# touch.net
KiCad netlist of a schematic drawn in Altium Designer
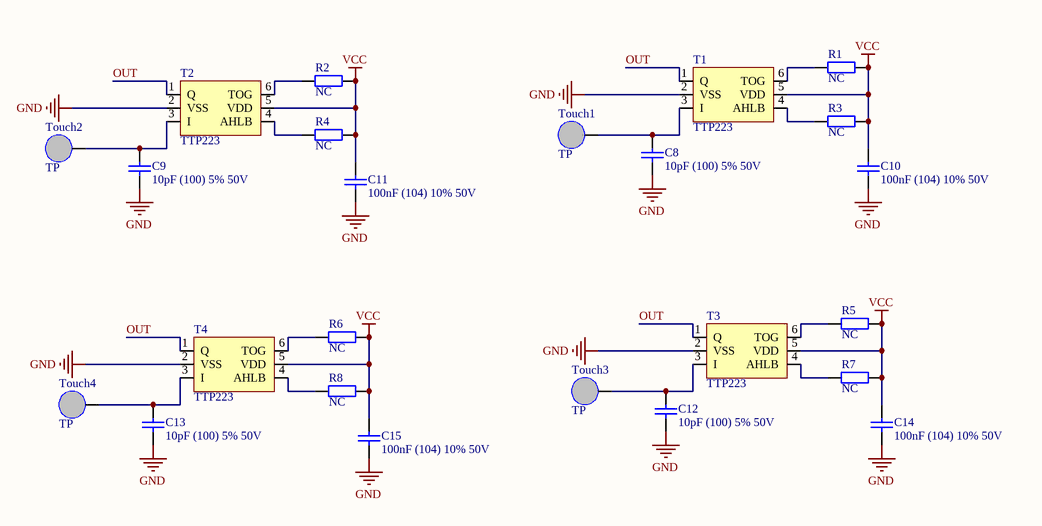
[diagram p0: touch.SchDoc]

(export (version "E")
  (design (tool "Eeschema 10.0.6"))
  (components
    (comp (ref "C8")
      (value "10pF (100) 5% 50V")
      (footprint "0603_C")
      (description "贴片电容")
      (libsource (lib "Miscellaneous Devices LC") (part "0603 10pF (100) 5% 50V"))
    )
    (comp (ref "C9")
      (value "10pF (100) 5% 50V")
      (footprint "0603_C")
      (description "贴片电容")
      (libsource (lib "Miscellaneous Devices LC") (part "0603 10pF (100) 5% 50V"))
    )
    (comp (ref "C10")
      (value "100nF (104) 10% 50V")
      (footprint "0603_C")
      (description "贴片电容")
      (libsource (lib "Miscellaneous Devices LC") (part "0603 100nF (104) 10% 50V"))
    )
    (comp (ref "C11")
      (value "100nF (104) 10% 50V")
      (footprint "0603_C")
      (description "贴片电容")
      (libsource (lib "Miscellaneous Devices LC") (part "0603 100nF (104) 10% 50V"))
    )
    (comp (ref "C12")
      (value "10pF (100) 5% 50V")
      (footprint "0603_C")
      (description "贴片电容")
      (libsource (lib "Miscellaneous Devices LC") (part "0603 10pF (100) 5% 50V"))
    )
    (comp (ref "C13")
      (value "10pF (100) 5% 50V")
      (footprint "0603_C")
      (description "贴片电容")
      (libsource (lib "Miscellaneous Devices LC") (part "0603 10pF (100) 5% 50V"))
    )
    (comp (ref "C14")
      (value "100nF (104) 10% 50V")
      (footprint "0603_C")
      (description "贴片电容")
      (libsource (lib "Miscellaneous Devices LC") (part "0603 100nF (104) 10% 50V"))
    )
    (comp (ref "C15")
      (value "100nF (104) 10% 50V")
      (footprint "0603_C")
      (description "贴片电容")
      (libsource (lib "Miscellaneous Devices LC") (part "0603 100nF (104) 10% 50V"))
    )
    (comp (ref "R1")
      (value "NC")
      (footprint "0603_R")
      (description "贴片电阻")
      (libsource (lib "Miscellaneous Devices LC") (part "0603 10KΩ (1002) 1%"))
    )
    (comp (ref "R2")
      (value "NC")
      (footprint "0603_R")
      (description "贴片电阻")
      (libsource (lib "Miscellaneous Devices LC") (part "0603 10KΩ (1002) 1%"))
    )
    (comp (ref "R3")
      (value "NC")
      (footprint "0603_R")
      (description "贴片电阻")
      (libsource (lib "Miscellaneous Devices LC") (part "0603 10KΩ (1002) 1%"))
    )
    (comp (ref "R4")
      (value "NC")
      (footprint "0603_R")
      (description "贴片电阻")
      (libsource (lib "Miscellaneous Devices LC") (part "0603 10KΩ (1002) 1%"))
    )
    (comp (ref "R5")
      (value "NC")
      (footprint "0603_R")
      (description "贴片电阻")
      (libsource (lib "Miscellaneous Devices LC") (part "0603 10KΩ (1002) 1%"))
    )
    (comp (ref "R6")
      (value "NC")
      (footprint "0603_R")
      (description "贴片电阻")
      (libsource (lib "Miscellaneous Devices LC") (part "0603 10KΩ (1002) 1%"))
    )
    (comp (ref "R7")
      (value "NC")
      (footprint "0603_R")
      (description "贴片电阻")
      (libsource (lib "Miscellaneous Devices LC") (part "0603 10KΩ (1002) 1%"))
    )
    (comp (ref "R8")
      (value "NC")
      (footprint "0603_R")
      (description "贴片电阻")
      (libsource (lib "Miscellaneous Devices LC") (part "0603 10KΩ (1002) 1%"))
    )
    (comp (ref "T1") (value "TTP223") (footprint "SOT-23-6") (libsource (lib "mylib") (part "TTP223")))
    (comp (ref "T2") (value "TTP223") (footprint "SOT-23-6") (libsource (lib "mylib") (part "TTP223")))
    (comp (ref "T3") (value "TTP223") (footprint "SOT-23-6") (libsource (lib "mylib") (part "TTP223")))
    (comp (ref "T4") (value "TTP223") (footprint "SOT-23-6") (libsource (lib "mylib") (part "TTP223")))
    (comp (ref "Touch1") (value "TP") (footprint "TP") (libsource (lib "mylib") (part "TP")))
    (comp (ref "Touch2") (value "TP") (footprint "TP") (libsource (lib "mylib") (part "TP")))
    (comp (ref "Touch3") (value "TP") (footprint "TP") (libsource (lib "mylib") (part "TP")))
    (comp (ref "Touch4") (value "TP") (footprint "TP") (libsource (lib "mylib") (part "TP")))
  )
  (nets
    (net (code "1") (name "/OUT") (class "Default")
      (node (ref "T1") (pin "1") (pinfunction "Q_1") (pintype "passive"))
      (node (ref "T2") (pin "1") (pinfunction "Q_1") (pintype "passive"))
      (node (ref "T3") (pin "1") (pinfunction "Q_1") (pintype "passive"))
      (node (ref "T4") (pin "1") (pinfunction "Q_1") (pintype "passive"))
    )
    (net (code "2") (name "GND") (class "Default")
      (node (ref "C10") (pin "1") (pinfunction "1_1") (pintype "passive"))
      (node (ref "C11") (pin "1") (pinfunction "1_1") (pintype "passive"))
      (node (ref "C12") (pin "1") (pinfunction "1_1") (pintype "passive"))
      (node (ref "C13") (pin "1") (pinfunction "1_1") (pintype "passive"))
      (node (ref "C14") (pin "1") (pinfunction "1_1") (pintype "passive"))
      (node (ref "C15") (pin "1") (pinfunction "1_1") (pintype "passive"))
      (node (ref "C8") (pin "1") (pinfunction "1_1") (pintype "passive"))
      (node (ref "C9") (pin "1") (pinfunction "1_1") (pintype "passive"))
      (node (ref "T1") (pin "2") (pinfunction "VSS_2") (pintype "passive"))
      (node (ref "T2") (pin "2") (pinfunction "VSS_2") (pintype "passive"))
      (node (ref "T3") (pin "2") (pinfunction "VSS_2") (pintype "passive"))
      (node (ref "T4") (pin "2") (pinfunction "VSS_2") (pintype "passive"))
    )
    (net (code "3") (name "Net-(T1-AHLB)") (class "Default")
      (node (ref "R3") (pin "1") (pinfunction "1_1") (pintype "passive"))
      (node (ref "T1") (pin "4") (pinfunction "AHLB_4") (pintype "passive"))
    )
    (net (code "4") (name "Net-(T1-I)") (class "Default")
      (node (ref "C8") (pin "2") (pinfunction "2_2") (pintype "passive"))
      (node (ref "T1") (pin "3") (pinfunction "I_3") (pintype "passive"))
      (node (ref "Touch1") (pin "1") (pinfunction "1_1") (pintype "passive"))
    )
    (net (code "5") (name "Net-(T1-TOG)") (class "Default")
      (node (ref "R1") (pin "1") (pinfunction "1_1") (pintype "passive"))
      (node (ref "T1") (pin "6") (pinfunction "TOG_6") (pintype "passive"))
    )
    (net (code "6") (name "Net-(T2-AHLB)") (class "Default")
      (node (ref "R4") (pin "1") (pinfunction "1_1") (pintype "passive"))
      (node (ref "T2") (pin "4") (pinfunction "AHLB_4") (pintype "passive"))
    )
    (net (code "7") (name "Net-(T2-I)") (class "Default")
      (node (ref "C9") (pin "2") (pinfunction "2_2") (pintype "passive"))
      (node (ref "T2") (pin "3") (pinfunction "I_3") (pintype "passive"))
      (node (ref "Touch2") (pin "1") (pinfunction "1_1") (pintype "passive"))
    )
    (net (code "8") (name "Net-(T2-TOG)") (class "Default")
      (node (ref "R2") (pin "1") (pinfunction "1_1") (pintype "passive"))
      (node (ref "T2") (pin "6") (pinfunction "TOG_6") (pintype "passive"))
    )
    (net (code "9") (name "Net-(T3-AHLB)") (class "Default")
      (node (ref "R7") (pin "1") (pinfunction "1_1") (pintype "passive"))
      (node (ref "T3") (pin "4") (pinfunction "AHLB_4") (pintype "passive"))
    )
    (net (code "10") (name "Net-(T3-I)") (class "Default")
      (node (ref "C12") (pin "2") (pinfunction "2_2") (pintype "passive"))
      (node (ref "T3") (pin "3") (pinfunction "I_3") (pintype "passive"))
      (node (ref "Touch3") (pin "1") (pinfunction "1_1") (pintype "passive"))
    )
    (net (code "11") (name "Net-(T3-TOG)") (class "Default")
      (node (ref "R5") (pin "1") (pinfunction "1_1") (pintype "passive"))
      (node (ref "T3") (pin "6") (pinfunction "TOG_6") (pintype "passive"))
    )
    (net (code "12") (name "Net-(T4-AHLB)") (class "Default")
      (node (ref "R8") (pin "1") (pinfunction "1_1") (pintype "passive"))
      (node (ref "T4") (pin "4") (pinfunction "AHLB_4") (pintype "passive"))
    )
    (net (code "13") (name "Net-(T4-I)") (class "Default")
      (node (ref "C13") (pin "2") (pinfunction "2_2") (pintype "passive"))
      (node (ref "T4") (pin "3") (pinfunction "I_3") (pintype "passive"))
      (node (ref "Touch4") (pin "1") (pinfunction "1_1") (pintype "passive"))
    )
    (net (code "14") (name "Net-(T4-TOG)") (class "Default")
      (node (ref "R6") (pin "1") (pinfunction "1_1") (pintype "passive"))
      (node (ref "T4") (pin "6") (pinfunction "TOG_6") (pintype "passive"))
    )
    (net (code "15") (name "VCC") (class "Default")
      (node (ref "C10") (pin "2") (pinfunction "2_2") (pintype "passive"))
      (node (ref "C11") (pin "2") (pinfunction "2_2") (pintype "passive"))
      (node (ref "C14") (pin "2") (pinfunction "2_2") (pintype "passive"))
      (node (ref "C15") (pin "2") (pinfunction "2_2") (pintype "passive"))
      (node (ref "R1") (pin "2") (pinfunction "2_2") (pintype "passive"))
      (node (ref "R2") (pin "2") (pinfunction "2_2") (pintype "passive"))
      (node (ref "R3") (pin "2") (pinfunction "2_2") (pintype "passive"))
      (node (ref "R4") (pin "2") (pinfunction "2_2") (pintype "passive"))
      (node (ref "R5") (pin "2") (pinfunction "2_2") (pintype "passive"))
      (node (ref "R6") (pin "2") (pinfunction "2_2") (pintype "passive"))
      (node (ref "R7") (pin "2") (pinfunction "2_2") (pintype "passive"))
      (node (ref "R8") (pin "2") (pinfunction "2_2") (pintype "passive"))
      (node (ref "T1") (pin "5") (pinfunction "VDD_5") (pintype "passive"))
      (node (ref "T2") (pin "5") (pinfunction "VDD_5") (pintype "passive"))
      (node (ref "T3") (pin "5") (pinfunction "VDD_5") (pintype "passive"))
      (node (ref "T4") (pin "5") (pinfunction "VDD_5") (pintype "passive"))
    )
  )
)
